# Overview.net
KiCad netlist of a schematic drawn in Altium Designer
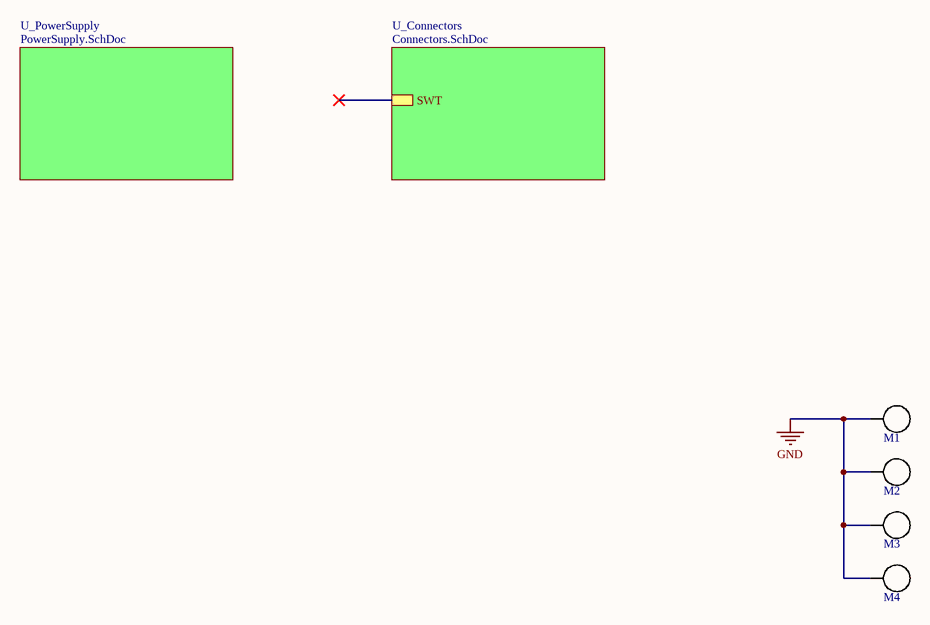
[diagram p0: Overview.SchDoc]

(export (version "E")
  (design (tool "Eeschema 10.0.6"))
  (components
    (comp (ref "M1")
      (value "TH-MOUNT-5mm_M2.5")
      (footprint "TH-MOUNT-HOLE_5mm_M2.5")
      (libsource (lib "JMD_Parts") (part "TH-MOUNT-5mm_M2.5"))
    )
    (comp (ref "M2")
      (value "TH-MOUNT-5mm_M2.5")
      (footprint "TH-MOUNT-HOLE_5mm_M2.5")
      (libsource (lib "JMD_Parts") (part "TH-MOUNT-5mm_M2.5"))
    )
    (comp (ref "M3")
      (value "TH-MOUNT-5mm_M2.5")
      (footprint "TH-MOUNT-HOLE_5mm_M2.5")
      (libsource (lib "JMD_Parts") (part "TH-MOUNT-5mm_M2.5"))
    )
    (comp (ref "M4")
      (value "TH-MOUNT-5mm_M2.5")
      (footprint "TH-MOUNT-HOLE_5mm_M2.5")
      (libsource (lib "JMD_Parts") (part "TH-MOUNT-5mm_M2.5"))
    )
  )
  (nets
    (net (code "2") (name "GND") (class "Default")
      (node (ref "M1") (pin "1") (pinfunction "1_1") (pintype "passive"))
      (node (ref "M2") (pin "1") (pinfunction "1_1") (pintype "passive"))
      (node (ref "M3") (pin "1") (pinfunction "1_1") (pintype "passive"))
      (node (ref "M4") (pin "1") (pinfunction "1_1") (pintype "passive"))
    )
  )
)
